# LED-PCB_DIG1.net
KiCad netlist of a schematic drawn in Altium Designer
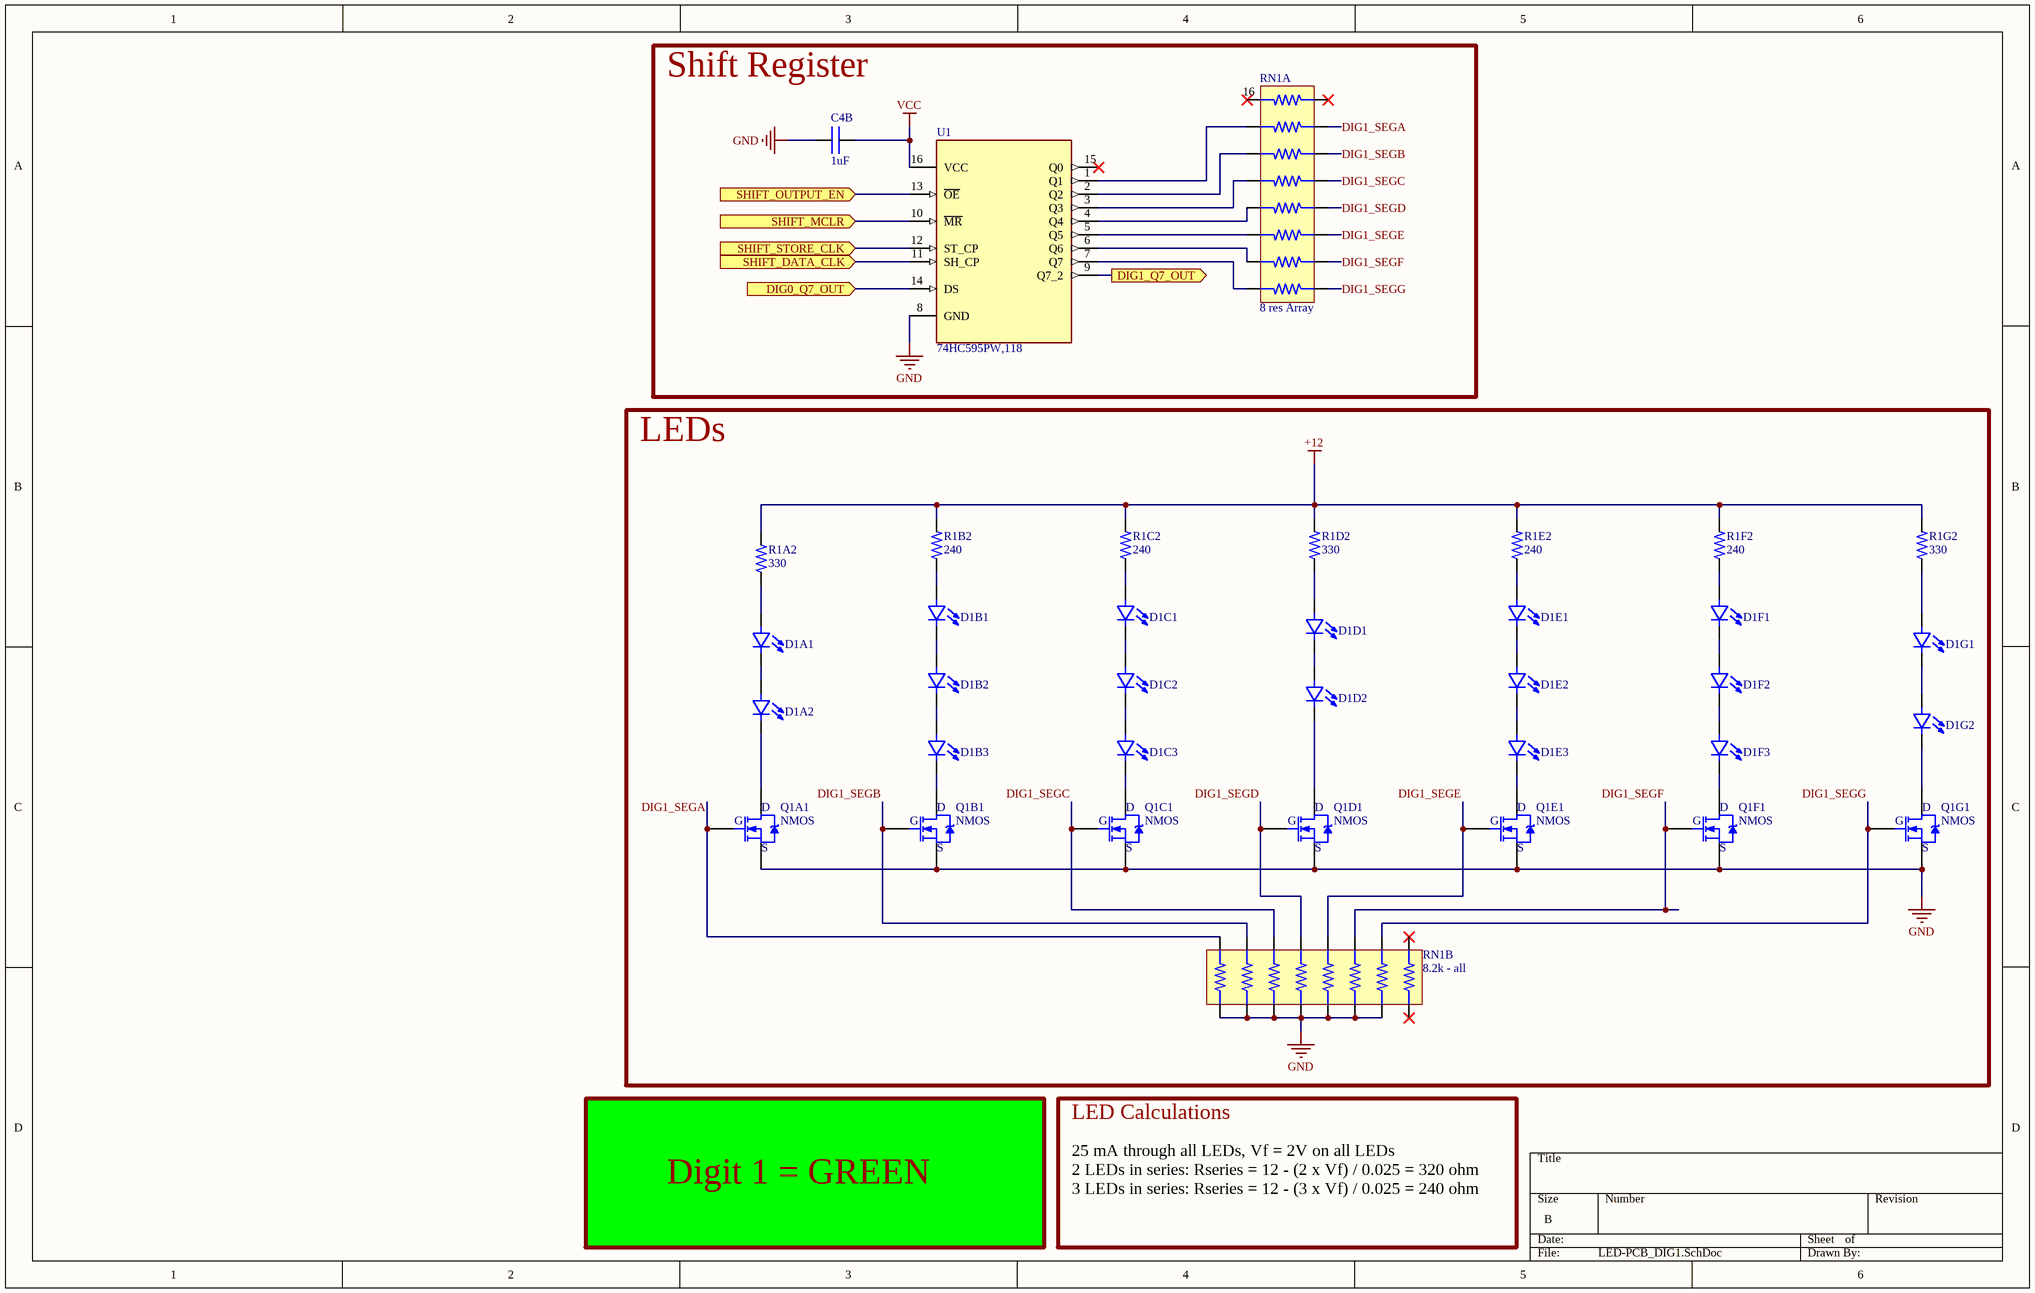
[diagram p0: LED-PCB_DIG1.SchDoc]

(export (version "E")
  (design (tool "Eeschema 10.0.6"))
  (components
    (comp (ref "C4B")
      (value "1uF")
      (footprint "sinking-clock:0402 CAP")
      (description "Capaicitor")
      (fields (field (name "MFR") "Samsung Microelectronics") (field (name "Comment") "CAP"))
      (libsource (lib "sinking-clock") (part "CAP"))
    )
    (comp (ref "D1A1")
      (value "LED - single")
      (footprint "sinking-clock:LED - 0603")
      (fields (field (name "MFR") "Wurth Elektronik"))
      (libsource (lib "sinking-clock") (part "LED - single"))
    )
    (comp (ref "D1A2")
      (value "LED - single")
      (footprint "sinking-clock:LED - 0603")
      (fields (field (name "MFR") "Wurth Elektronik"))
      (libsource (lib "sinking-clock") (part "LED - single"))
    )
    (comp (ref "D1B1")
      (value "LED - single")
      (footprint "sinking-clock:LED - 0603")
      (fields (field (name "MFR") "Wurth Elektronik"))
      (libsource (lib "sinking-clock") (part "LED - single"))
    )
    (comp (ref "D1B2")
      (value "LED - single")
      (footprint "sinking-clock:LED - 0603")
      (fields (field (name "MFR") "Wurth Elektronik"))
      (libsource (lib "sinking-clock") (part "LED - single"))
    )
    (comp (ref "D1B3")
      (value "LED - single")
      (footprint "sinking-clock:LED - 0603")
      (fields (field (name "MFR") "Wurth Elektronik"))
      (libsource (lib "sinking-clock") (part "LED - single"))
    )
    (comp (ref "D1C1")
      (value "LED - single")
      (footprint "sinking-clock:LED - 0603")
      (fields (field (name "MFR") "Wurth Elektronik"))
      (libsource (lib "sinking-clock") (part "LED - single"))
    )
    (comp (ref "D1C2")
      (value "LED - single")
      (footprint "sinking-clock:LED - 0603")
      (fields (field (name "MFR") "Wurth Elektronik"))
      (libsource (lib "sinking-clock") (part "LED - single"))
    )
    (comp (ref "D1C3")
      (value "LED - single")
      (footprint "sinking-clock:LED - 0603")
      (fields (field (name "MFR") "Wurth Elektronik"))
      (libsource (lib "sinking-clock") (part "LED - single"))
    )
    (comp (ref "D1D1")
      (value "LED - single")
      (footprint "sinking-clock:LED - 0603")
      (fields (field (name "MFR") "Wurth Elektronik"))
      (libsource (lib "sinking-clock") (part "LED - single"))
    )
    (comp (ref "D1D2")
      (value "LED - single")
      (footprint "sinking-clock:LED - 0603")
      (fields (field (name "MFR") "Wurth Elektronik"))
      (libsource (lib "sinking-clock") (part "LED - single"))
    )
    (comp (ref "D1E1")
      (value "LED - single")
      (footprint "sinking-clock:LED - 0603")
      (fields (field (name "MFR") "Wurth Elektronik"))
      (libsource (lib "sinking-clock") (part "LED - single"))
    )
    (comp (ref "D1E2")
      (value "LED - single")
      (footprint "sinking-clock:LED - 0603")
      (fields (field (name "MFR") "Wurth Elektronik"))
      (libsource (lib "sinking-clock") (part "LED - single"))
    )
    (comp (ref "D1E3")
      (value "LED - single")
      (footprint "sinking-clock:LED - 0603")
      (fields (field (name "MFR") "Wurth Elektronik"))
      (libsource (lib "sinking-clock") (part "LED - single"))
    )
    (comp (ref "D1F1")
      (value "LED - single")
      (footprint "sinking-clock:LED - 0603")
      (fields (field (name "MFR") "Wurth Elektronik"))
      (libsource (lib "sinking-clock") (part "LED - single"))
    )
    (comp (ref "D1F2")
      (value "LED - single")
      (footprint "sinking-clock:LED - 0603")
      (fields (field (name "MFR") "Wurth Elektronik"))
      (libsource (lib "sinking-clock") (part "LED - single"))
    )
    (comp (ref "D1F3")
      (value "LED - single")
      (footprint "sinking-clock:LED - 0603")
      (fields (field (name "MFR") "Wurth Elektronik"))
      (libsource (lib "sinking-clock") (part "LED - single"))
    )
    (comp (ref "D1G1")
      (value "LED - single")
      (footprint "sinking-clock:LED - 0603")
      (fields (field (name "MFR") "Wurth Elektronik"))
      (libsource (lib "sinking-clock") (part "LED - single"))
    )
    (comp (ref "D1G2")
      (value "LED - single")
      (footprint "sinking-clock:LED - 0603")
      (fields (field (name "MFR") "Wurth Elektronik"))
      (libsource (lib "sinking-clock") (part "LED - single"))
    )
    (comp (ref "Q1A1")
      (value "NMOS")
      (footprint "sinking-clock:SOT-23")
      (description "N-Channel MOSFET")
      (fields (field (name "MFR") "Diodes Incorporated"))
      (libsource (lib "sinking-clock") (part "NMOS"))
    )
    (comp (ref "Q1B1")
      (value "NMOS")
      (footprint "sinking-clock:SOT-23")
      (description "N-Channel MOSFET")
      (fields (field (name "MFR") "Diodes Incorporated"))
      (libsource (lib "sinking-clock") (part "NMOS"))
    )
    (comp (ref "Q1C1")
      (value "NMOS")
      (footprint "sinking-clock:SOT-23")
      (description "N-Channel MOSFET")
      (fields (field (name "MFR") "Diodes Incorporated"))
      (libsource (lib "sinking-clock") (part "NMOS"))
    )
    (comp (ref "Q1D1")
      (value "NMOS")
      (footprint "sinking-clock:SOT-23")
      (description "N-Channel MOSFET")
      (fields (field (name "MFR") "Diodes Incorporated"))
      (libsource (lib "sinking-clock") (part "NMOS"))
    )
    (comp (ref "Q1E1")
      (value "NMOS")
      (footprint "sinking-clock:SOT-23")
      (description "N-Channel MOSFET")
      (fields (field (name "MFR") "Diodes Incorporated"))
      (libsource (lib "sinking-clock") (part "NMOS"))
    )
    (comp (ref "Q1F1")
      (value "NMOS")
      (footprint "sinking-clock:SOT-23")
      (description "N-Channel MOSFET")
      (fields (field (name "MFR") "Diodes Incorporated"))
      (libsource (lib "sinking-clock") (part "NMOS"))
    )
    (comp (ref "Q1G1")
      (value "NMOS")
      (footprint "sinking-clock:SOT-23")
      (description "N-Channel MOSFET")
      (fields (field (name "MFR") "Diodes Incorporated"))
      (libsource (lib "sinking-clock") (part "NMOS"))
    )
    (comp (ref "R1A2")
      (value "330")
      (footprint "sinking-clock:0402 RES")
      (description "Resistor")
      (fields (field (name "MFR") "YAGEO") (field (name "Comment") "RES"))
      (libsource (lib "sinking-clock") (part "RES"))
    )
    (comp (ref "R1B2")
      (value "240")
      (footprint "sinking-clock:0402 RES")
      (description "Resistor")
      (fields (field (name "MFR") "YAGEO") (field (name "Comment") "RES"))
      (libsource (lib "sinking-clock") (part "RES"))
    )
    (comp (ref "R1C2")
      (value "240")
      (footprint "sinking-clock:0402 RES")
      (description "Resistor")
      (fields (field (name "MFR") "YAGEO") (field (name "Comment") "RES"))
      (libsource (lib "sinking-clock") (part "RES"))
    )
    (comp (ref "R1D2")
      (value "330")
      (footprint "sinking-clock:0402 RES")
      (description "Resistor")
      (fields (field (name "MFR") "YAGEO") (field (name "Comment") "RES"))
      (libsource (lib "sinking-clock") (part "RES"))
    )
    (comp (ref "R1E2")
      (value "240")
      (footprint "sinking-clock:0402 RES")
      (description "Resistor")
      (fields (field (name "MFR") "YAGEO") (field (name "Comment") "RES"))
      (libsource (lib "sinking-clock") (part "RES"))
    )
    (comp (ref "R1F2")
      (value "240")
      (footprint "sinking-clock:0402 RES")
      (description "Resistor")
      (fields (field (name "MFR") "YAGEO") (field (name "Comment") "RES"))
      (libsource (lib "sinking-clock") (part "RES"))
    )
    (comp (ref "R1G2")
      (value "330")
      (footprint "sinking-clock:0402 RES")
      (description "Resistor")
      (fields (field (name "MFR") "YAGEO") (field (name "Comment") "RES"))
      (libsource (lib "sinking-clock") (part "RES"))
    )
    (comp (ref "RN1A")
      (value "8 res Array")
      (footprint "sinking-clock:EXB2HV331JV")
      (fields (field (name "MFR") "Panasonic Microelectronics"))
      (libsource (lib "sinking-clock") (part "8 res Array"))
    )
    (comp (ref "RN1B")
      (value "8.2k - all")
      (footprint "sinking-clock:MNR18ERAPJ822")
      (fields (field (name "MFR") "Rohm Semiconductor"))
      (libsource (lib "sinking-clock") (part "MNR18ERAPJ822"))
    )
    (comp (ref "U1")
      (value "74HC595PW,118")
      (footprint "sinking-clock:16-TSSOP")
      (description "Shift Shift Register 1 Element 8 Bit 16-TSSOP")
      (libsource (lib "sinking-clock") (part "74HC595PW,118"))
    )
  )
  (nets
    (net (code "1") (name "+12") (class "Default")
      (node (ref "R1A2") (pin "2") (pinfunction "2_2") (pintype "passive"))
      (node (ref "R1B2") (pin "2") (pinfunction "2_2") (pintype "passive"))
      (node (ref "R1C2") (pin "2") (pinfunction "2_2") (pintype "passive"))
      (node (ref "R1D2") (pin "2") (pinfunction "2_2") (pintype "passive"))
      (node (ref "R1E2") (pin "2") (pinfunction "2_2") (pintype "passive"))
      (node (ref "R1F2") (pin "2") (pinfunction "2_2") (pintype "passive"))
      (node (ref "R1G2") (pin "2") (pinfunction "2_2") (pintype "passive"))
    )
    (net (code "2") (name "/DIG0_Q7_OUT") (class "Default")
      (node (ref "U1") (pin "14") (pinfunction "DS_14") (pintype "input"))
    )
    (net (code "3") (name "/DIG1_Q7_OUT") (class "Default")
      (node (ref "U1") (pin "9") (pinfunction "Q7_2_9") (pintype "output"))
    )
    (net (code "4") (name "/DIG1_SEGA") (class "Default")
      (node (ref "Q1A1") (pin "1") (pinfunction "G_1") (pintype "passive"))
      (node (ref "RN1A") (pin "2") (pinfunction "2_2") (pintype "passive"))
      (node (ref "RN1B") (pin "16") (pinfunction "16_16") (pintype "passive"))
    )
    (net (code "5") (name "/DIG1_SEGB") (class "Default")
      (node (ref "Q1B1") (pin "1") (pinfunction "G_1") (pintype "passive"))
      (node (ref "RN1A") (pin "3") (pinfunction "3_3") (pintype "passive"))
      (node (ref "RN1B") (pin "15") (pinfunction "15_15") (pintype "passive"))
    )
    (net (code "6") (name "/DIG1_SEGC") (class "Default")
      (node (ref "Q1C1") (pin "1") (pinfunction "G_1") (pintype "passive"))
      (node (ref "RN1A") (pin "4") (pinfunction "4_4") (pintype "passive"))
      (node (ref "RN1B") (pin "14") (pinfunction "14_14") (pintype "passive"))
    )
    (net (code "7") (name "/DIG1_SEGD") (class "Default")
      (node (ref "Q1D1") (pin "1") (pinfunction "G_1") (pintype "passive"))
      (node (ref "RN1A") (pin "5") (pinfunction "5_5") (pintype "passive"))
      (node (ref "RN1B") (pin "13") (pinfunction "13_13") (pintype "passive"))
    )
    (net (code "8") (name "/DIG1_SEGE") (class "Default")
      (node (ref "Q1E1") (pin "1") (pinfunction "G_1") (pintype "passive"))
      (node (ref "RN1A") (pin "6") (pinfunction "6_6") (pintype "passive"))
      (node (ref "RN1B") (pin "12") (pinfunction "12_12") (pintype "passive"))
    )
    (net (code "9") (name "/DIG1_SEGF") (class "Default")
      (node (ref "Q1F1") (pin "1") (pinfunction "G_1") (pintype "passive"))
      (node (ref "RN1A") (pin "7") (pinfunction "7_7") (pintype "passive"))
      (node (ref "RN1B") (pin "11") (pinfunction "11_11") (pintype "passive"))
    )
    (net (code "10") (name "/DIG1_SEGG") (class "Default")
      (node (ref "Q1G1") (pin "1") (pinfunction "G_1") (pintype "passive"))
      (node (ref "RN1A") (pin "8") (pinfunction "8_8") (pintype "passive"))
      (node (ref "RN1B") (pin "10") (pinfunction "10_10") (pintype "passive"))
    )
    (net (code "11") (name "/SHIFT_DATA_CLK") (class "Default")
      (node (ref "U1") (pin "11") (pinfunction "SH_CP_11") (pintype "input"))
    )
    (net (code "12") (name "/SHIFT_MCLR") (class "Default")
      (node (ref "U1") (pin "10") (pinfunction "~{MR}_10") (pintype "input"))
    )
    (net (code "13") (name "/SHIFT_OUTPUT_EN") (class "Default")
      (node (ref "U1") (pin "13") (pinfunction "~{OE}_13") (pintype "input"))
    )
    (net (code "14") (name "/SHIFT_STORE_CLK") (class "Default")
      (node (ref "U1") (pin "12") (pinfunction "ST_CP_12") (pintype "input"))
    )
    (net (code "15") (name "GND") (class "Default")
      (node (ref "C4B") (pin "1") (pinfunction "1_1") (pintype "passive"))
      (node (ref "Q1A1") (pin "2") (pinfunction "S_2") (pintype "passive"))
      (node (ref "Q1B1") (pin "2") (pinfunction "S_2") (pintype "passive"))
      (node (ref "Q1C1") (pin "2") (pinfunction "S_2") (pintype "passive"))
      (node (ref "Q1D1") (pin "2") (pinfunction "S_2") (pintype "passive"))
      (node (ref "Q1E1") (pin "2") (pinfunction "S_2") (pintype "passive"))
      (node (ref "Q1F1") (pin "2") (pinfunction "S_2") (pintype "passive"))
      (node (ref "Q1G1") (pin "2") (pinfunction "S_2") (pintype "passive"))
      (node (ref "RN1B") (pin "1") (pinfunction "1_1") (pintype "passive"))
      (node (ref "RN1B") (pin "2") (pinfunction "2_2") (pintype "passive"))
      (node (ref "RN1B") (pin "3") (pinfunction "3_3") (pintype "passive"))
      (node (ref "RN1B") (pin "4") (pinfunction "4_4") (pintype "passive"))
      (node (ref "RN1B") (pin "5") (pinfunction "5_5") (pintype "passive"))
      (node (ref "RN1B") (pin "6") (pinfunction "6_6") (pintype "passive"))
      (node (ref "RN1B") (pin "7") (pinfunction "7_7") (pintype "passive"))
      (node (ref "U1") (pin "8") (pinfunction "GND_8") (pintype "passive"))
    )
    (net (code "16") (name "Net-(D1A1-A)") (class "Default")
      (node (ref "D1A1") (pin "1") (pinfunction "A_1") (pintype "passive"))
      (node (ref "R1A2") (pin "1") (pinfunction "1_1") (pintype "passive"))
    )
    (net (code "17") (name "Net-(D1A1-C)") (class "Default")
      (node (ref "D1A1") (pin "2") (pinfunction "C_2") (pintype "passive"))
      (node (ref "D1A2") (pin "1") (pinfunction "A_1") (pintype "passive"))
    )
    (net (code "18") (name "Net-(D1A2-C)") (class "Default")
      (node (ref "D1A2") (pin "2") (pinfunction "C_2") (pintype "passive"))
      (node (ref "Q1A1") (pin "3") (pinfunction "D_3") (pintype "passive"))
    )
    (net (code "19") (name "Net-(D1B1-A)") (class "Default")
      (node (ref "D1B1") (pin "1") (pinfunction "A_1") (pintype "passive"))
      (node (ref "R1B2") (pin "1") (pinfunction "1_1") (pintype "passive"))
    )
    (net (code "20") (name "Net-(D1B1-C)") (class "Default")
      (node (ref "D1B1") (pin "2") (pinfunction "C_2") (pintype "passive"))
      (node (ref "D1B2") (pin "1") (pinfunction "A_1") (pintype "passive"))
    )
    (net (code "21") (name "Net-(D1B2-C)") (class "Default")
      (node (ref "D1B2") (pin "2") (pinfunction "C_2") (pintype "passive"))
      (node (ref "D1B3") (pin "1") (pinfunction "A_1") (pintype "passive"))
    )
    (net (code "22") (name "Net-(D1B3-C)") (class "Default")
      (node (ref "D1B3") (pin "2") (pinfunction "C_2") (pintype "passive"))
      (node (ref "Q1B1") (pin "3") (pinfunction "D_3") (pintype "passive"))
    )
    (net (code "23") (name "Net-(D1C1-A)") (class "Default")
      (node (ref "D1C1") (pin "1") (pinfunction "A_1") (pintype "passive"))
      (node (ref "R1C2") (pin "1") (pinfunction "1_1") (pintype "passive"))
    )
    (net (code "24") (name "Net-(D1C1-C)") (class "Default")
      (node (ref "D1C1") (pin "2") (pinfunction "C_2") (pintype "passive"))
      (node (ref "D1C2") (pin "1") (pinfunction "A_1") (pintype "passive"))
    )
    (net (code "25") (name "Net-(D1C2-C)") (class "Default")
      (node (ref "D1C2") (pin "2") (pinfunction "C_2") (pintype "passive"))
      (node (ref "D1C3") (pin "1") (pinfunction "A_1") (pintype "passive"))
    )
    (net (code "26") (name "Net-(D1C3-C)") (class "Default")
      (node (ref "D1C3") (pin "2") (pinfunction "C_2") (pintype "passive"))
      (node (ref "Q1C1") (pin "3") (pinfunction "D_3") (pintype "passive"))
    )
    (net (code "27") (name "Net-(D1D1-A)") (class "Default")
      (node (ref "D1D1") (pin "1") (pinfunction "A_1") (pintype "passive"))
      (node (ref "R1D2") (pin "1") (pinfunction "1_1") (pintype "passive"))
    )
    (net (code "28") (name "Net-(D1D1-C)") (class "Default")
      (node (ref "D1D1") (pin "2") (pinfunction "C_2") (pintype "passive"))
      (node (ref "D1D2") (pin "1") (pinfunction "A_1") (pintype "passive"))
    )
    (net (code "29") (name "Net-(D1D2-C)") (class "Default")
      (node (ref "D1D2") (pin "2") (pinfunction "C_2") (pintype "passive"))
      (node (ref "Q1D1") (pin "3") (pinfunction "D_3") (pintype "passive"))
    )
    (net (code "30") (name "Net-(D1E1-A)") (class "Default")
      (node (ref "D1E1") (pin "1") (pinfunction "A_1") (pintype "passive"))
      (node (ref "R1E2") (pin "1") (pinfunction "1_1") (pintype "passive"))
    )
    (net (code "31") (name "Net-(D1E1-C)") (class "Default")
      (node (ref "D1E1") (pin "2") (pinfunction "C_2") (pintype "passive"))
      (node (ref "D1E2") (pin "1") (pinfunction "A_1") (pintype "passive"))
    )
    (net (code "32") (name "Net-(D1E2-C)") (class "Default")
      (node (ref "D1E2") (pin "2") (pinfunction "C_2") (pintype "passive"))
      (node (ref "D1E3") (pin "1") (pinfunction "A_1") (pintype "passive"))
    )
    (net (code "33") (name "Net-(D1E3-C)") (class "Default")
      (node (ref "D1E3") (pin "2") (pinfunction "C_2") (pintype "passive"))
      (node (ref "Q1E1") (pin "3") (pinfunction "D_3") (pintype "passive"))
    )
    (net (code "34") (name "Net-(D1F1-A)") (class "Default")
      (node (ref "D1F1") (pin "1") (pinfunction "A_1") (pintype "passive"))
      (node (ref "R1F2") (pin "1") (pinfunction "1_1") (pintype "passive"))
    )
    (net (code "35") (name "Net-(D1F1-C)") (class "Default")
      (node (ref "D1F1") (pin "2") (pinfunction "C_2") (pintype "passive"))
      (node (ref "D1F2") (pin "1") (pinfunction "A_1") (pintype "passive"))
    )
    (net (code "36") (name "Net-(D1F2-C)") (class "Default")
      (node (ref "D1F2") (pin "2") (pinfunction "C_2") (pintype "passive"))
      (node (ref "D1F3") (pin "1") (pinfunction "A_1") (pintype "passive"))
    )
    (net (code "37") (name "Net-(D1F3-C)") (class "Default")
      (node (ref "D1F3") (pin "2") (pinfunction "C_2") (pintype "passive"))
      (node (ref "Q1F1") (pin "3") (pinfunction "D_3") (pintype "passive"))
    )
    (net (code "38") (name "Net-(D1G1-A)") (class "Default")
      (node (ref "D1G1") (pin "1") (pinfunction "A_1") (pintype "passive"))
      (node (ref "R1G2") (pin "1") (pinfunction "1_1") (pintype "passive"))
    )
    (net (code "39") (name "Net-(D1G1-C)") (class "Default")
      (node (ref "D1G1") (pin "2") (pinfunction "C_2") (pintype "passive"))
      (node (ref "D1G2") (pin "1") (pinfunction "A_1") (pintype "passive"))
    )
    (net (code "40") (name "Net-(D1G2-C)") (class "Default")
      (node (ref "D1G2") (pin "2") (pinfunction "C_2") (pintype "passive"))
      (node (ref "Q1G1") (pin "3") (pinfunction "D_3") (pintype "passive"))
    )
    (net (code "41") (name "Net-(U1-Q1)") (class "Default")
      (node (ref "RN1A") (pin "15") (pinfunction "15_15") (pintype "passive"))
      (node (ref "U1") (pin "1") (pinfunction "Q1_1") (pintype "output"))
    )
    (net (code "42") (name "Net-(U1-Q2)") (class "Default")
      (node (ref "RN1A") (pin "14") (pinfunction "14_14") (pintype "passive"))
      (node (ref "U1") (pin "2") (pinfunction "Q2_2") (pintype "output"))
    )
    (net (code "43") (name "Net-(U1-Q3)") (class "Default")
      (node (ref "RN1A") (pin "13") (pinfunction "13_13") (pintype "passive"))
      (node (ref "U1") (pin "3") (pinfunction "Q3_3") (pintype "output"))
    )
    (net (code "44") (name "Net-(U1-Q4)") (class "Default")
      (node (ref "RN1A") (pin "12") (pinfunction "12_12") (pintype "passive"))
      (node (ref "U1") (pin "4") (pinfunction "Q4_4") (pintype "output"))
    )
    (net (code "45") (name "Net-(U1-Q5)") (class "Default")
      (node (ref "RN1A") (pin "11") (pinfunction "11_11") (pintype "passive"))
      (node (ref "U1") (pin "5") (pinfunction "Q5_5") (pintype "output"))
    )
    (net (code "46") (name "Net-(U1-Q6)") (class "Default")
      (node (ref "RN1A") (pin "10") (pinfunction "10_10") (pintype "passive"))
      (node (ref "U1") (pin "6") (pinfunction "Q6_6") (pintype "output"))
    )
    (net (code "47") (name "Net-(U1-Q7)") (class "Default")
      (node (ref "RN1A") (pin "9") (pinfunction "9_9") (pintype "passive"))
      (node (ref "U1") (pin "7") (pinfunction "Q7_7") (pintype "output"))
    )
    (net (code "48") (name "VCC") (class "Default")
      (node (ref "C4B") (pin "2") (pinfunction "2_2") (pintype "passive"))
      (node (ref "U1") (pin "16") (pinfunction "VCC_16") (pintype "power_in"))
    )
    (net (code "49") (name "unconnected-(RN1A-Pad1)") (class "Default")
      (node (ref "RN1A") (pin "1") (pinfunction "1_1") (pintype "passive+no_connect"))
    )
    (net (code "50") (name "unconnected-(RN1A-Pad16)") (class "Default")
      (node (ref "RN1A") (pin "16") (pinfunction "16_16") (pintype "passive+no_connect"))
    )
    (net (code "51") (name "unconnected-(RN1B-Pad8)") (class "Default")
      (node (ref "RN1B") (pin "8") (pinfunction "8_8") (pintype "passive+no_connect"))
    )
    (net (code "52") (name "unconnected-(RN1B-Pad9)") (class "Default")
      (node (ref "RN1B") (pin "9") (pinfunction "9_9") (pintype "passive+no_connect"))
    )
    (net (code "53") (name "unconnected-(U1-Q0-Pad15)") (class "Default")
      (node (ref "U1") (pin "15") (pinfunction "Q0_15") (pintype "output+no_connect"))
    )
  )
)
